# main.net
KiCad netlist of a schematic drawn in Altium Designer
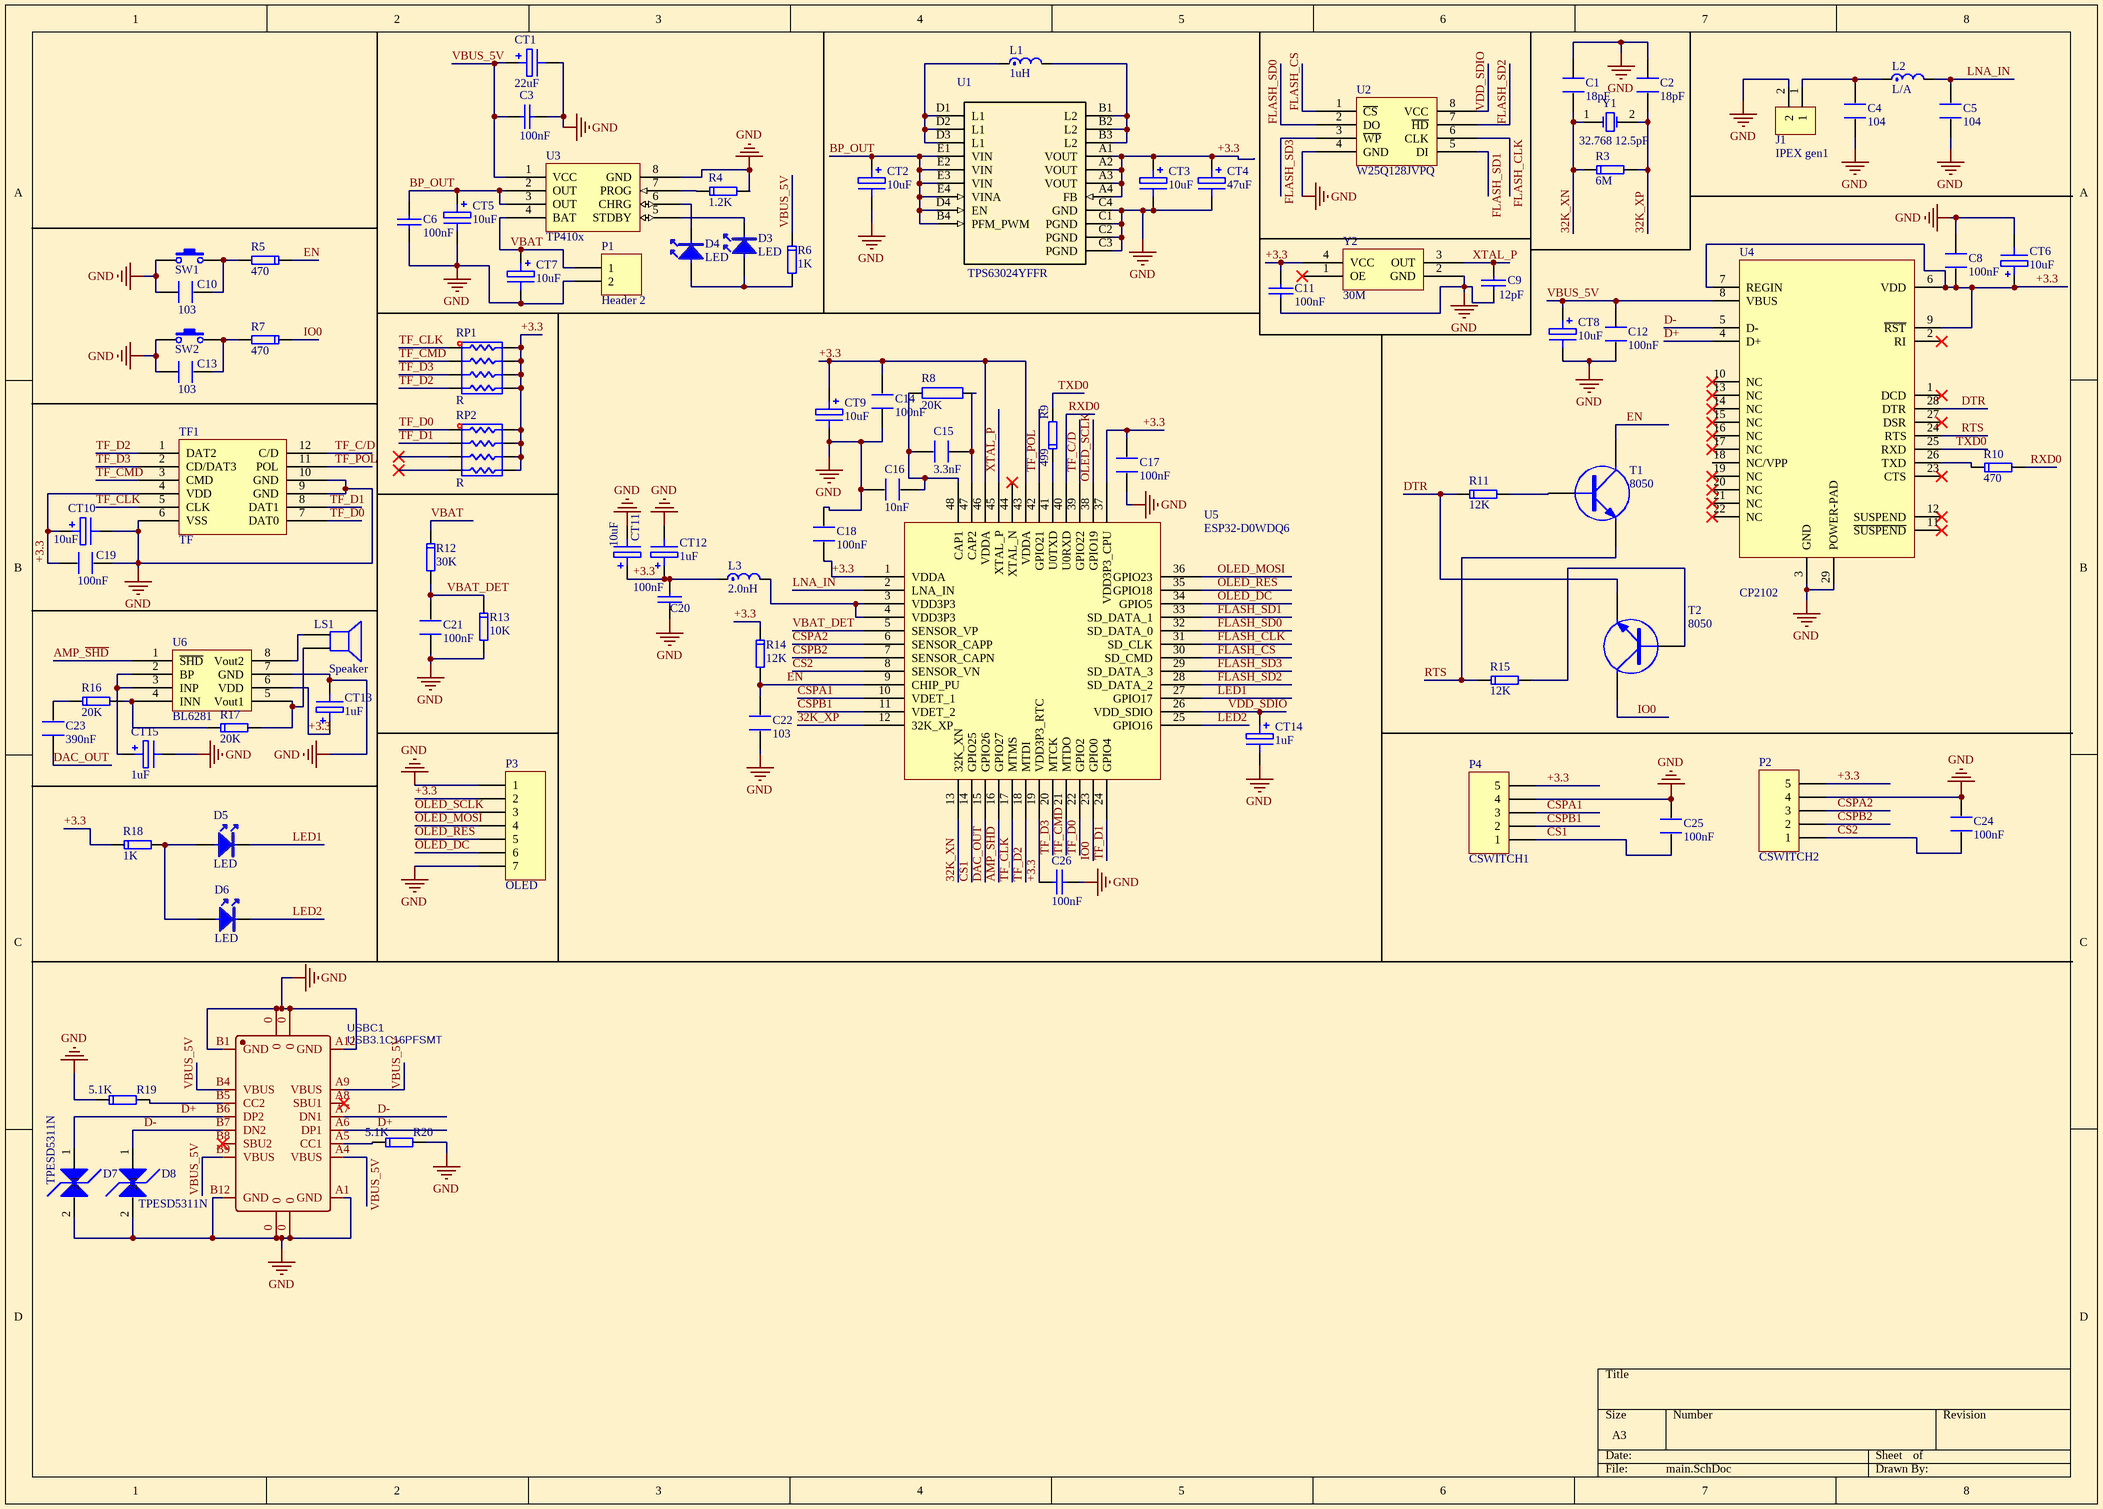
[diagram p0: main.SchDoc]

(export (version "E")
  (design (tool "Eeschema 10.0.6"))
  (components
    (comp (ref "C1") (value "18pF") (footprint "C0603") (libsource (lib "常用2") (part "Capacitor")))
    (comp (ref "C2") (value "18pF") (footprint "C0603") (libsource (lib "常用2") (part "Capacitor")))
    (comp (ref "C3") (value "100nF") (footprint "C0603") (libsource (lib "常用") (part "CAP1")))
    (comp (ref "C4") (value "104") (footprint "C0603") (libsource (lib "常用2") (part "Capacitor")))
    (comp (ref "C5") (value "104") (footprint "C0603") (libsource (lib "常用2") (part "Capacitor")))
    (comp (ref "C6") (value "100nF") (footprint "C0603") (libsource (lib "常用") (part "CAP1")))
    (comp (ref "C8") (value "100nF") (footprint "C0603") (libsource (lib "常用") (part "Capacitor")))
    (comp (ref "C9") (value "12pF") (footprint "C0603") (libsource (lib "常用") (part "CAP1")))
    (comp (ref "C10") (value "103") (footprint "C0603") (libsource (lib "常用2") (part "Capacitor")))
    (comp (ref "C11") (value "100nF") (footprint "C0603") (libsource (lib "常用") (part "CAP1")))
    (comp (ref "C12") (value "100nF") (footprint "C0603") (libsource (lib "常用") (part "Capacitor")))
    (comp (ref "C13") (value "103") (footprint "C0603") (libsource (lib "常用2") (part "Capacitor")))
    (comp (ref "C14") (value "100nF") (footprint "C0603") (libsource (lib "常用2") (part "Capacitor")))
    (comp (ref "C15") (value "3.3nF") (footprint "C0603") (libsource (lib "常用") (part "Capacitor")))
    (comp (ref "C16") (value "10nF") (footprint "C0603") (libsource (lib "常用") (part "Capacitor")))
    (comp (ref "C17") (value "100nF") (footprint "C0603") (libsource (lib "常用2") (part "Capacitor")))
    (comp (ref "C18") (value "100nF") (footprint "C0603") (libsource (lib "常用2") (part "Capacitor")))
    (comp (ref "C19") (value "100nF") (footprint "C0603") (libsource (lib "常用") (part "Capacitor")))
    (comp (ref "C20") (value "100nF") (footprint "C0603") (libsource (lib "常用") (part "CAP1")))
    (comp (ref "C21") (value "100nF") (footprint "C0603") (libsource (lib "常用") (part "Capacitor")))
    (comp (ref "C22") (value "103") (footprint "C0603") (libsource (lib "常用2") (part "Capacitor")))
    (comp (ref "C23") (value "390nF") (footprint "C0603") (libsource (lib "常用2") (part "Capacitor")))
    (comp (ref "C24") (value "100nF") (footprint "C0603") (libsource (lib "常用") (part "Capacitor")))
    (comp (ref "C25") (value "100nF") (footprint "C0603") (libsource (lib "常用") (part "Capacitor")))
    (comp (ref "C26") (value "100nF") (footprint "C0603") (libsource (lib "常用") (part "CAP1")))
    (comp (ref "CT1") (value "22uF") (footprint "C1206") (libsource (lib "常用") (part "CAP Tantalum")))
    (comp (ref "CT2") (value "10uF") (footprint "C1206") (libsource (lib "常用") (part "CAP Tantalum")))
    (comp (ref "CT3") (value "10uF") (footprint "C1206") (libsource (lib "常用") (part "CAP Tantalum")))
    (comp (ref "CT4") (value "47uF") (footprint "C1206") (libsource (lib "常用") (part "CAP Tantalum")))
    (comp (ref "CT5") (value "10uF") (footprint "C1206") (libsource (lib "常用") (part "CAP Tantalum")))
    (comp (ref "CT6") (value "10uF") (footprint "C1206") (libsource (lib "常用") (part "CAP Tantalum")))
    (comp (ref "CT7") (value "10uF") (footprint "C1206") (libsource (lib "常用") (part "CAP Tantalum")))
    (comp (ref "CT8") (value "10uF") (footprint "C1206") (libsource (lib "常用") (part "CAP Tantalum")))
    (comp (ref "CT9") (value "10uF") (footprint "C1206") (libsource (lib "常用") (part "CAP Tantalum")))
    (comp (ref "CT10") (value "10uF") (footprint "C1206") (libsource (lib "常用") (part "CAP Tantalum")))
    (comp (ref "CT11") (value "10uF") (footprint "C1206") (libsource (lib "常用") (part "CAP Tantalum")))
    (comp (ref "CT12") (value "1uF") (footprint "C1206") (libsource (lib "常用") (part "CAP Tantalum")))
    (comp (ref "CT13") (value "1uF") (footprint "C1206") (libsource (lib "常用") (part "CAP Tantalum")))
    (comp (ref "CT14") (value "1uF") (footprint "C1206") (libsource (lib "常用") (part "CAP Tantalum")))
    (comp (ref "CT15") (value "1uF") (footprint "C1206") (libsource (lib "常用") (part "CAP Tantalum")))
    (comp (ref "D3") (value "LED") (footprint "LED_1206") (libsource (lib "常用") (part "LED")))
    (comp (ref "D4") (value "LED") (footprint "LED_1206") (libsource (lib "常用") (part "LED")))
    (comp (ref "D5") (value "LED") (footprint "LED_1206") (libsource (lib "常用") (part "LED")))
    (comp (ref "D6") (value "LED") (footprint "LED_1206") (libsource (lib "常用") (part "LED")))
    (comp (ref "D7") (value "TPESD5311N") (footprint "DFN1006-2") (libsource (lib "常用2") (part "TPESD5311N")))
    (comp (ref "D8") (value "TPESD5311N") (footprint "DFN1006-2") (libsource (lib "常用2") (part "TPESD5311N")))
    (comp (ref "J1") (value "IPEX gen1") (footprint "IPEX gen1") (libsource (lib "常用2") (part "IPEX gen1")))
    (comp (ref "L1") (value "1uH") (footprint "L0520") (libsource (lib "常用") (part "INDUTOR")))
    (comp (ref "L2") (value "L/A") (footprint "L0603") (libsource (lib "常用") (part "INDUTOR")))
    (comp (ref "L3") (value "2.0nH") (footprint "L0603") (libsource (lib "常用") (part "INDUTOR")))
    (comp (ref "LS1")
      (value "Speaker")
      (footprint "PIN2")
      (description "Loudspeaker")
      (fields (field (name "PUBLISHER") "Altium Limited"))
      (libsource (lib "Miscellaneous Devices") (part "Speaker"))
    )
    (comp (ref "P1")
      (value "Header 2")
      (footprint "HDR1X2")
      (description "Header, 2-Pin")
      (fields (field (name "PUBLISHER") "Altium Limited"))
      (libsource (lib "Miscellaneous Connectors") (part "Header 2"))
    )
    (comp (ref "P2")
      (value "CSWITCH2")
      (footprint "HDR1X5")
      (description "Header, 5-Pin")
      (fields (field (name "PUBLISHER") "Altium Limited"))
      (libsource (lib "Miscellaneous Connectors") (part "Header 5"))
    )
    (comp (ref "P3")
      (value "OLED")
      (footprint "HDR1X7")
      (description "Header, 7-Pin")
      (fields (field (name "PUBLISHER") "Altium Limited"))
      (libsource (lib "Miscellaneous Connectors") (part "Header 7"))
    )
    (comp (ref "P4")
      (value "CSWITCH1")
      (footprint "HDR1X5")
      (description "Header, 5-Pin")
      (fields (field (name "PUBLISHER") "Altium Limited"))
      (libsource (lib "Miscellaneous Connectors") (part "Header 5"))
    )
    (comp (ref "R3") (value "6M") (footprint "R0603") (libsource (lib "常用2") (part "Resistor")))
    (comp (ref "R4") (value "1.2K") (footprint "R0603") (libsource (lib "常用") (part "Resistor")))
    (comp (ref "R5") (value "470") (footprint "R0603") (libsource (lib "常用2") (part "Resistor")))
    (comp (ref "R6") (value "1K") (footprint "R0603") (libsource (lib "常用") (part "Resistor")))
    (comp (ref "R7") (value "470") (footprint "R0603") (libsource (lib "常用2") (part "Resistor")))
    (comp (ref "R8") (value "20K") (footprint "0603") (description "电阻") (libsource (lib "常用") (part "RES")))
    (comp (ref "R9") (value "499") (footprint "R0603") (libsource (lib "常用") (part "Resistor")))
    (comp (ref "R10") (value "470") (footprint "R0603") (libsource (lib "常用") (part "Resistor")))
    (comp (ref "R11") (value "12K") (footprint "R0603") (libsource (lib "常用") (part "Resistor")))
    (comp (ref "R12") (value "30K") (footprint "R0603") (libsource (lib "常用2") (part "Resistor")))
    (comp (ref "R13") (value "10K") (footprint "R0603") (libsource (lib "常用2") (part "Resistor")))
    (comp (ref "R14") (value "12K") (footprint "R0603") (libsource (lib "常用2") (part "Resistor")))
    (comp (ref "R15") (value "12K") (footprint "R0603") (libsource (lib "常用") (part "Resistor")))
    (comp (ref "R16") (value "20K") (footprint "R0603") (libsource (lib "常用2") (part "Resistor")))
    (comp (ref "R17") (value "20K") (footprint "R0603") (libsource (lib "常用2") (part "Resistor")))
    (comp (ref "R18") (value "1K") (footprint "R0603") (libsource (lib "常用2") (part "Resistor")))
    (comp (ref "R19") (value "5.1K") (footprint "R0603") (libsource (lib "常用") (part "Resistor")))
    (comp (ref "R20") (value "5.1K") (footprint "R0603") (libsource (lib "常用") (part "Resistor")))
    (comp (ref "RP1")
      (value "R")
      (footprint "RP4")
      (description "Isolated Resistor Network")
      (fields (field (name "PUBLISHER") "Altium Limited"))
      (libsource (lib "常用") (part "RP4"))
    )
    (comp (ref "RP2")
      (value "R")
      (footprint "RP4")
      (description "Isolated Resistor Network")
      (fields (field (name "PUBLISHER") "Altium Limited"))
      (libsource (lib "常用") (part "RP4"))
    )
    (comp (ref "SW1")
      (value "switch")
      (footprint "microswitch")
      (description "微动开关")
      (libsource (lib "常用2") (part "microswitch"))
    )
    (comp (ref "SW2")
      (value "switch")
      (footprint "microswitch")
      (description "微动开关")
      (libsource (lib "常用2") (part "microswitch"))
    )
    (comp (ref "T1")
      (value "8050")
      (footprint "STO-23")
      (description "NPN型三极管")
      (libsource (lib "常用") (part "8050"))
    )
    (comp (ref "T2")
      (value "8050")
      (footprint "STO-23")
      (description "NPN型三极管")
      (libsource (lib "常用") (part "8050"))
    )
    (comp (ref "TF1") (value "TF") (footprint "TF_3") (libsource (lib "TF") (part "TF3")))
    (comp (ref "U1")
      (value "TPS63024YFFR")
      (footprint "YFF0020AJAF")
      (description "No Description Available")
      (fields
        (field (name "ALTERNATE_PARTNUMBER") "TPS63024YFFT")
        (field (name "MANUFACTURER") "Texas Instruments")
        (field (name "COPYRIGHT") "Copyright (C) 2018 Accelerated Designs. All rights reserved")
      )
      (libsource (lib "TPS63024YFFR") (part "TPS63024YFFR"))
    )
    (comp (ref "U2")
      (value "W25Q128JVPQ")
      (footprint "WSON-8_5x6mm")
      (libsource (lib "FLASH") (part "W25Q128JVPQ"))
    )
    (comp (ref "U3") (value "TP410x") (footprint "DFN-8_EP_3x3mm") (libsource (lib "TP4102") (part "TP410x")))
    (comp (ref "U4")
      (value "CP2102")
      (footprint "QFN-28")
      (description "USB to TTL")
      (libsource (lib "常用2") (part "CP2102"))
    )
    (comp (ref "U5")
      (value "ESP32-D0WDQ6")
      (footprint "QFN-48_6x6x04P")
      (libsource (lib "ESP32") (part "ESP32-D0WDQ6"))
    )
    (comp (ref "U6")
      (value "BL6281")
      (footprint "MSOP-8")
      (description "国产功放")
      (libsource (lib "常用2") (part "BL6281"))
    )
    (comp (ref "USBC1")
      (value "USB3.1C16PFSMT")
      (footprint "TYPE-C-USB-17")
      (libsource (lib "type-c-m") (part "USB3.1C16PFSMT"))
    )
    (comp (ref "Y1")
      (value "32.768 12.5pF")
      (footprint "SMD-3215_2P FC - 135")
      (description "Crystal Oscillator")
      (libsource (lib "常用晶振") (part "XTAL"))
    )
    (comp (ref "Y2")
      (value "30M")
      (footprint "SMD-2016-4P")
      (description "Simple Package Xtal Oscillator")
      (libsource (lib "常用晶振") (part "XTAL-SPXO"))
    )
  )
  (nets
    (net (code "1") (name "/+3.3") (class "Default")
      (node (ref "C11") (pin "2") (pinfunction "2_2") (pintype "passive"))
      (node (ref "C14") (pin "2") (pintype "passive"))
      (node (ref "C17") (pin "2") (pintype "passive"))
      (node (ref "C18") (pin "1") (pintype "passive"))
      (node (ref "C19") (pin "2") (pintype "passive"))
      (node (ref "C20") (pin "1") (pinfunction "1_1") (pintype "passive"))
      (node (ref "C26") (pin "1") (pinfunction "1_1") (pintype "passive"))
      (node (ref "C8") (pin "1") (pintype "passive"))
      (node (ref "CT10") (pin "1") (pinfunction "1_1") (pintype "passive"))
      (node (ref "CT11") (pin "1") (pinfunction "1_1") (pintype "passive"))
      (node (ref "CT12") (pin "1") (pinfunction "1_1") (pintype "passive"))
      (node (ref "CT13") (pin "1") (pinfunction "1_1") (pintype "passive"))
      (node (ref "CT3") (pin "1") (pinfunction "1_1") (pintype "passive"))
      (node (ref "CT4") (pin "1") (pinfunction "1_1") (pintype "passive"))
      (node (ref "CT6") (pin "1") (pinfunction "1_1") (pintype "passive"))
      (node (ref "CT9") (pin "1") (pinfunction "1_1") (pintype "passive"))
      (node (ref "L3") (pin "1") (pinfunction "1_1") (pintype "passive"))
      (node (ref "P2") (pin "5") (pinfunction "5_5") (pintype "passive"))
      (node (ref "P3") (pin "2") (pinfunction "2_2") (pintype "passive"))
      (node (ref "P4") (pin "5") (pinfunction "5_5") (pintype "passive"))
      (node (ref "R14") (pin "1") (pinfunction "1_1") (pintype "passive"))
      (node (ref "R18") (pin "1") (pinfunction "1_1") (pintype "passive"))
      (node (ref "RP1") (pin "5") (pinfunction "5_5") (pintype "passive"))
      (node (ref "RP1") (pin "6") (pinfunction "6_6") (pintype "passive"))
      (node (ref "RP1") (pin "7") (pinfunction "7_7") (pintype "passive"))
      (node (ref "RP1") (pin "8") (pinfunction "8_8") (pintype "passive"))
      (node (ref "RP2") (pin "5") (pinfunction "5_5") (pintype "passive"))
      (node (ref "RP2") (pin "6") (pinfunction "6_6") (pintype "passive"))
      (node (ref "RP2") (pin "7") (pinfunction "7_7") (pintype "passive"))
      (node (ref "RP2") (pin "8") (pinfunction "8_8") (pintype "passive"))
      (node (ref "TF1") (pin "4") (pinfunction "VDD_4") (pintype "passive"))
      (node (ref "U1") (pin "A1") (pinfunction "VOUT_A1") (pintype "power_in"))
      (node (ref "U1") (pin "A2") (pinfunction "VOUT_A2") (pintype "power_in"))
      (node (ref "U1") (pin "A3") (pinfunction "VOUT_A3") (pintype "power_in"))
      (node (ref "U1") (pin "A4") (pinfunction "FB_A4") (pintype "input"))
      (node (ref "U4") (pin "6") (pinfunction "VDD_6") (pintype "passive"))
      (node (ref "U4") (pin "7") (pinfunction "REGIN_7") (pintype "passive"))
      (node (ref "U4") (pin "9") (pinfunction "~{RST}_9") (pintype "passive"))
      (node (ref "U5") (pin "1") (pinfunction "VDDA_1") (pintype "passive"))
      (node (ref "U5") (pin "19") (pinfunction "VDD3P3_RTC_19") (pintype "passive"))
      (node (ref "U5") (pin "37") (pinfunction "VDD3P3_CPU_37") (pintype "passive"))
      (node (ref "U5") (pin "43") (pinfunction "VDDA_43") (pintype "passive"))
      (node (ref "U5") (pin "46") (pinfunction "VDDA_46") (pintype "passive"))
      (node (ref "U6") (pin "6") (pinfunction "VDD_6") (pintype "passive"))
      (node (ref "Y2") (pin "4") (pinfunction "VCC_4") (pintype "passive"))
    )
    (net (code "2") (name "/32K_XN") (class "Default")
      (node (ref "C1") (pin "2") (pintype "passive"))
      (node (ref "R3") (pin "1") (pinfunction "1_1") (pintype "passive"))
      (node (ref "U5") (pin "13") (pinfunction "32K_XN_13") (pintype "passive"))
      (node (ref "Y1") (pin "1") (pinfunction "1_1") (pintype "passive"))
    )
    (net (code "3") (name "/32K_XP") (class "Default")
      (node (ref "C2") (pin "2") (pintype "passive"))
      (node (ref "R3") (pin "2") (pinfunction "2_2") (pintype "passive"))
      (node (ref "U5") (pin "12") (pinfunction "32K_XP_12") (pintype "passive"))
      (node (ref "Y1") (pin "2") (pinfunction "2_2") (pintype "passive"))
    )
    (net (code "4") (name "/AMP_~{SHD}") (class "Default")
      (node (ref "U5") (pin "16") (pinfunction "GPIO27_16") (pintype "passive"))
      (node (ref "U6") (pin "1") (pinfunction "~{SHD}_1") (pintype "passive"))
    )
    (net (code "5") (name "/BP_OUT") (class "Default")
      (node (ref "C6") (pin "2") (pinfunction "2_2") (pintype "passive"))
      (node (ref "CT2") (pin "1") (pinfunction "1_1") (pintype "passive"))
      (node (ref "CT5") (pin "1") (pinfunction "1_1") (pintype "passive"))
      (node (ref "U1") (pin "B4") (pinfunction "PFM_PWM_B4") (pintype "input"))
      (node (ref "U1") (pin "D4") (pinfunction "EN_D4") (pintype "input"))
      (node (ref "U1") (pin "E1") (pinfunction "VIN_E1") (pintype "power_in"))
      (node (ref "U1") (pin "E2") (pinfunction "VIN_E2") (pintype "power_in"))
      (node (ref "U1") (pin "E3") (pinfunction "VIN_E3") (pintype "power_in"))
      (node (ref "U1") (pin "E4") (pinfunction "VINA_E4") (pintype "input"))
      (node (ref "U3") (pin "2") (pinfunction "OUT_2") (pintype "power_in"))
      (node (ref "U3") (pin "3") (pinfunction "OUT_3") (pintype "power_in"))
    )
    (net (code "6") (name "/CS1") (class "Default")
      (node (ref "C25") (pin "2") (pintype "passive"))
      (node (ref "P4") (pin "1") (pinfunction "1_1") (pintype "passive"))
      (node (ref "U5") (pin "14") (pinfunction "GPIO25_14") (pintype "passive"))
    )
    (net (code "7") (name "/CS2") (class "Default")
      (node (ref "C24") (pin "2") (pintype "passive"))
      (node (ref "P2") (pin "1") (pinfunction "1_1") (pintype "passive"))
      (node (ref "U5") (pin "8") (pinfunction "SENSOR_VN_8") (pintype "passive"))
    )
    (net (code "8") (name "/CSPA1") (class "Default")
      (node (ref "P4") (pin "3") (pinfunction "3_3") (pintype "passive"))
      (node (ref "U5") (pin "10") (pinfunction "VDET_1_10") (pintype "passive"))
    )
    (net (code "9") (name "/CSPA2") (class "Default")
      (node (ref "P2") (pin "3") (pinfunction "3_3") (pintype "passive"))
      (node (ref "U5") (pin "6") (pinfunction "SENSOR_CAPP_6") (pintype "passive"))
    )
    (net (code "10") (name "/CSPB1") (class "Default")
      (node (ref "P4") (pin "2") (pinfunction "2_2") (pintype "passive"))
      (node (ref "U5") (pin "11") (pinfunction "VDET_2_11") (pintype "passive"))
    )
    (net (code "11") (name "/CSPB2") (class "Default")
      (node (ref "P2") (pin "2") (pinfunction "2_2") (pintype "passive"))
      (node (ref "U5") (pin "7") (pinfunction "SENSOR_CAPN_7") (pintype "passive"))
    )
    (net (code "12") (name "/D+") (class "Default")
      (node (ref "D7") (pin "1") (pinfunction "1_1") (pintype "passive"))
      (node (ref "U4") (pin "4") (pinfunction "D+_4") (pintype "passive"))
      (node (ref "USBC1") (pin "A6") (pinfunction "DP1_A6") (pintype "passive"))
      (node (ref "USBC1") (pin "B6") (pinfunction "DP2_B6") (pintype "passive"))
    )
    (net (code "13") (name "/D-") (class "Default")
      (node (ref "D8") (pin "1") (pinfunction "1_1") (pintype "passive"))
      (node (ref "U4") (pin "5") (pinfunction "D-_5") (pintype "passive"))
      (node (ref "USBC1") (pin "A7") (pinfunction "DN1_A7") (pintype "passive"))
      (node (ref "USBC1") (pin "B7") (pinfunction "DN2_B7") (pintype "passive"))
    )
    (net (code "14") (name "/DAC_OUT") (class "Default")
      (node (ref "C23") (pin "1") (pintype "passive"))
      (node (ref "U5") (pin "15") (pinfunction "GPIO26_15") (pintype "passive"))
    )
    (net (code "15") (name "/DTR") (class "Default")
      (node (ref "R11") (pin "1") (pinfunction "1_1") (pintype "passive"))
      (node (ref "T2") (pin "1") (pinfunction "E_1") (pintype "passive"))
      (node (ref "U4") (pin "28") (pinfunction "DTR_28") (pintype "passive"))
    )
    (net (code "16") (name "/EN") (class "Default")
      (node (ref "C22") (pin "2") (pintype "passive"))
      (node (ref "R14") (pin "2") (pinfunction "2_2") (pintype "passive"))
      (node (ref "R5") (pin "1") (pinfunction "1_1") (pintype "passive"))
      (node (ref "T1") (pin "3") (pinfunction "C_3") (pintype "passive"))
      (node (ref "U5") (pin "9") (pinfunction "CHIP_PU_9") (pintype "passive"))
    )
    (net (code "17") (name "/FLASH_CLK") (class "Default")
      (node (ref "U2") (pin "6") (pinfunction "CLK_6") (pintype "passive"))
      (node (ref "U5") (pin "31") (pinfunction "SD_CLK_31") (pintype "passive"))
    )
    (net (code "18") (name "/FLASH_CS") (class "Default")
      (node (ref "U2") (pin "1") (pinfunction "~{CS}_1") (pintype "passive"))
      (node (ref "U5") (pin "30") (pinfunction "SD_CMD_30") (pintype "passive"))
    )
    (net (code "19") (name "/FLASH_SD0") (class "Default")
      (node (ref "U2") (pin "2") (pinfunction "DO_2") (pintype "passive"))
      (node (ref "U5") (pin "32") (pinfunction "SD_DATA_0_32") (pintype "passive"))
    )
    (net (code "20") (name "/FLASH_SD1") (class "Default")
      (node (ref "U2") (pin "5") (pinfunction "DI_5") (pintype "passive"))
      (node (ref "U5") (pin "33") (pinfunction "SD_DATA_1_33") (pintype "passive"))
    )
    (net (code "21") (name "/FLASH_SD2") (class "Default")
      (node (ref "U2") (pin "7") (pinfunction "~{HD}_7") (pintype "passive"))
      (node (ref "U5") (pin "28") (pinfunction "SD_DATA_2_28") (pintype "passive"))
    )
    (net (code "22") (name "/FLASH_SD3") (class "Default")
      (node (ref "U2") (pin "3") (pinfunction "~{WP}_3") (pintype "passive"))
      (node (ref "U5") (pin "29") (pinfunction "SD_DATA_3_29") (pintype "passive"))
    )
    (net (code "23") (name "/IO0") (class "Default")
      (node (ref "R7") (pin "1") (pinfunction "1_1") (pintype "passive"))
      (node (ref "T2") (pin "3") (pinfunction "C_3") (pintype "passive"))
      (node (ref "U5") (pin "23") (pinfunction "GPIO0_23") (pintype "passive"))
    )
    (net (code "24") (name "/LED1") (class "Default")
      (node (ref "D5") (pin "2") (pinfunction "2_2") (pintype "passive"))
      (node (ref "U5") (pin "27") (pinfunction "GPIO17_27") (pintype "passive"))
    )
    (net (code "25") (name "/LED2") (class "Default")
      (node (ref "D6") (pin "2") (pinfunction "2_2") (pintype "passive"))
      (node (ref "U5") (pin "25") (pinfunction "GPIO16_25") (pintype "passive"))
    )
    (net (code "26") (name "/LNA_IN") (class "Default")
      (node (ref "C5") (pin "2") (pintype "passive"))
      (node (ref "L2") (pin "2") (pinfunction "2_2") (pintype "passive"))
      (node (ref "U5") (pin "2") (pinfunction "LNA_IN_2") (pintype "passive"))
    )
    (net (code "27") (name "/OLED_DC") (class "Default")
      (node (ref "P3") (pin "6") (pinfunction "6_6") (pintype "passive"))
      (node (ref "U5") (pin "34") (pinfunction "GPIO5_34") (pintype "passive"))
    )
    (net (code "28") (name "/OLED_MOSI") (class "Default")
      (node (ref "P3") (pin "4") (pinfunction "4_4") (pintype "passive"))
      (node (ref "U5") (pin "36") (pinfunction "GPIO23_36") (pintype "passive"))
    )
    (net (code "29") (name "/OLED_RES") (class "Default")
      (node (ref "P3") (pin "5") (pinfunction "5_5") (pintype "passive"))
      (node (ref "U5") (pin "35") (pinfunction "GPIO18_35") (pintype "passive"))
    )
    (net (code "30") (name "/OLED_SCLK") (class "Default")
      (node (ref "P3") (pin "3") (pinfunction "3_3") (pintype "passive"))
      (node (ref "U5") (pin "38") (pinfunction "GPIO19_38") (pintype "passive"))
    )
    (net (code "31") (name "/RTS") (class "Default")
      (node (ref "R15") (pin "1") (pinfunction "1_1") (pintype "passive"))
      (node (ref "T1") (pin "1") (pinfunction "E_1") (pintype "passive"))
      (node (ref "U4") (pin "24") (pinfunction "RTS_24") (pintype "passive"))
    )
    (net (code "32") (name "/RXD0") (class "Default")
      (node (ref "R10") (pin "2") (pinfunction "2_2") (pintype "passive"))
      (node (ref "U5") (pin "40") (pinfunction "U0RXD_40") (pintype "passive"))
    )
    (net (code "33") (name "/TF_CLK") (class "Default")
      (node (ref "RP1") (pin "1") (pinfunction "1_1") (pintype "passive"))
      (node (ref "TF1") (pin "5") (pinfunction "CLK_5") (pintype "passive"))
      (node (ref "U5") (pin "17") (pinfunction "MTMS_17") (pintype "passive"))
    )
    (net (code "34") (name "/TF_CMD") (class "Default")
      (node (ref "RP1") (pin "2") (pinfunction "2_2") (pintype "passive"))
      (node (ref "TF1") (pin "3") (pinfunction "CMD_3") (pintype "passive"))
      (node (ref "U5") (pin "21") (pinfunction "MTDO_21") (pintype "passive"))
    )
    (net (code "35") (name "/TF_C{slash}D") (class "Default")
      (node (ref "TF1") (pin "12") (pinfunction "C/D_12") (pintype "passive"))
      (node (ref "U5") (pin "39") (pinfunction "GPIO22_39") (pintype "passive"))
    )
    (net (code "36") (name "/TF_D0") (class "Default")
      (node (ref "RP2") (pin "1") (pinfunction "1_1") (pintype "passive"))
      (node (ref "TF1") (pin "7") (pinfunction "DAT0_7") (pintype "passive"))
      (node (ref "U5") (pin "22") (pinfunction "GPIO2_22") (pintype "passive"))
    )
    (net (code "37") (name "/TF_D1") (class "Default")
      (node (ref "RP2") (pin "2") (pinfunction "2_2") (pintype "passive"))
      (node (ref "TF1") (pin "8") (pinfunction "DAT1_8") (pintype "passive"))
      (node (ref "U5") (pin "24") (pinfunction "GPIO4_24") (pintype "passive"))
    )
    (net (code "38") (name "/TF_D2") (class "Default")
      (node (ref "RP1") (pin "4") (pinfunction "4_4") (pintype "passive"))
      (node (ref "TF1") (pin "1") (pinfunction "DAT2_1") (pintype "passive"))
      (node (ref "U5") (pin "18") (pinfunction "MTDI_18") (pintype "passive"))
    )
    (net (code "39") (name "/TF_D3") (class "Default")
      (node (ref "RP1") (pin "3") (pinfunction "3_3") (pintype "passive"))
      (node (ref "TF1") (pin "2") (pinfunction "CD/DAT3_2") (pintype "passive"))
      (node (ref "U5") (pin "20") (pinfunction "MTCK_20") (pintype "passive"))
    )
    (net (code "40") (name "/TF_POL") (class "Default")
      (node (ref "TF1") (pin "11") (pinfunction "POL_11") (pintype "passive"))
      (node (ref "U5") (pin "42") (pinfunction "GPIO21_42") (pintype "passive"))
    )
    (net (code "41") (name "/TXD0") (class "Default")
      (node (ref "R9") (pin "2") (pinfunction "2_2") (pintype "passive"))
      (node (ref "U4") (pin "25") (pinfunction "RXD_25") (pintype "passive"))
    )
    (net (code "42") (name "/VBAT") (class "Default")
      (node (ref "CT7") (pin "1") (pinfunction "1_1") (pintype "passive"))
      (node (ref "P1") (pin "1") (pinfunction "1_1") (pintype "passive"))
      (node (ref "R12") (pin "1") (pinfunction "1_1") (pintype "passive"))
      (node (ref "U3") (pin "4") (pinfunction "BAT_4") (pintype "power_in"))
    )
    (net (code "43") (name "/VBAT_DET") (class "Default")
      (node (ref "C21") (pin "1") (pintype "passive"))
      (node (ref "R12") (pin "2") (pinfunction "2_2") (pintype "passive"))
      (node (ref "R13") (pin "1") (pinfunction "1_1") (pintype "passive"))
      (node (ref "U5") (pin "5") (pinfunction "SENSOR_VP_5") (pintype "passive"))
    )
    (net (code "44") (name "/VBUS_5V") (class "Default")
      (node (ref "C12") (pin "2") (pintype "passive"))
      (node (ref "C3") (pin "1") (pinfunction "1_1") (pintype "passive"))
      (node (ref "CT1") (pin "1") (pinfunction "1_1") (pintype "passive"))
      (node (ref "CT8") (pin "1") (pinfunction "1_1") (pintype "passive"))
      (node (ref "R6") (pin "1") (pinfunction "1_1") (pintype "passive"))
      (node (ref "U3") (pin "1") (pinfunction "VCC_1") (pintype "passive"))
      (node (ref "U4") (pin "8") (pinfunction "VBUS_8") (pintype "passive"))
      (node (ref "USBC1") (pin "A4") (pinfunction "VBUS_A4") (pintype "passive"))
      (node (ref "USBC1") (pin "A9") (pinfunction "VBUS_A9") (pintype "passive"))
      (node (ref "USBC1") (pin "B4") (pinfunction "VBUS_B4") (pintype "passive"))
      (node (ref "USBC1") (pin "B9") (pinfunction "VBUS_B9") (pintype "passive"))
    )
    (net (code "45") (name "/VDD_SDIO") (class "Default")
      (node (ref "CT14") (pin "1") (pinfunction "1_1") (pintype "passive"))
      (node (ref "U2") (pin "8") (pinfunction "VCC_8") (pintype "passive"))
      (node (ref "U5") (pin "26") (pinfunction "VDD_SDIO_26") (pintype "passive"))
    )
    (net (code "46") (name "/XTAL_P") (class "Default")
      (node (ref "C9") (pin "2") (pinfunction "2_2") (pintype "passive"))
      (node (ref "U5") (pin "45") (pinfunction "XTAL_P_45") (pintype "passive"))
      (node (ref "Y2") (pin "3") (pinfunction "OUT_3") (pintype "passive"))
    )
    (net (code "47") (name "GND") (class "Default")
      (node (ref "C1") (pin "1") (pintype "passive"))
      (node (ref "C10") (pin "1") (pintype "passive"))
      (node (ref "C11") (pin "1") (pinfunction "1_1") (pintype "passive"))
      (node (ref "C12") (pin "1") (pintype "passive"))
      (node (ref "C13") (pin "1") (pintype "passive"))
      (node (ref "C14") (pin "1") (pintype "passive"))
      (node (ref "C16") (pin "2") (pintype "passive"))
      (node (ref "C17") (pin "1") (pintype "passive"))
      (node (ref "C18") (pin "2") (pintype "passive"))
      (node (ref "C19") (pin "1") (pintype "passive"))
      (node (ref "C2") (pin "1") (pintype "passive"))
      (node (ref "C20") (pin "2") (pinfunction "2_2") (pintype "passive"))
      (node (ref "C21") (pin "2") (pintype "passive"))
      (node (ref "C22") (pin "1") (pintype "passive"))
      (node (ref "C24") (pin "1") (pintype "passive"))
      (node (ref "C25") (pin "1") (pintype "passive"))
      (node (ref "C26") (pin "2") (pinfunction "2_2") (pintype "passive"))
      (node (ref "C3") (pin "2") (pinfunction "2_2") (pintype "passive"))
      (node (ref "C4") (pin "1") (pintype "passive"))
      (node (ref "C5") (pin "1") (pintype "passive"))
      (node (ref "C6") (pin "1") (pinfunction "1_1") (pintype "passive"))
      (node (ref "C8") (pin "2") (pintype "passive"))
      (node (ref "C9") (pin "1") (pinfunction "1_1") (pintype "passive"))
      (node (ref "CT1") (pin "2") (pinfunction "2_2") (pintype "passive"))
      (node (ref "CT10") (pin "2") (pinfunction "2_2") (pintype "passive"))
      (node (ref "CT11") (pin "2") (pinfunction "2_2") (pintype "passive"))
      (node (ref "CT12") (pin "2") (pinfunction "2_2") (pintype "passive"))
      (node (ref "CT13") (pin "2") (pinfunction "2_2") (pintype "passive"))
      (node (ref "CT14") (pin "2") (pinfunction "2_2") (pintype "passive"))
      (node (ref "CT15") (pin "2") (pinfunction "2_2") (pintype "passive"))
      (node (ref "CT2") (pin "2") (pinfunction "2_2") (pintype "passive"))
      (node (ref "CT3") (pin "2") (pinfunction "2_2") (pintype "passive"))
      (node (ref "CT4") (pin "2") (pinfunction "2_2") (pintype "passive"))
      (node (ref "CT5") (pin "2") (pinfunction "2_2") (pintype "passive"))
      (node (ref "CT6") (pin "2") (pinfunction "2_2") (pintype "passive"))
      (node (ref "CT7") (pin "2") (pinfunction "2_2") (pintype "passive"))
      (node (ref "CT8") (pin "2") (pinfunction "2_2") (pintype "passive"))
      (node (ref "CT9") (pin "2") (pinfunction "2_2") (pintype "passive"))
      (node (ref "D7") (pin "2") (pinfunction "2_2") (pintype "passive"))
      (node (ref "D8") (pin "2") (pinfunction "2_2") (pintype "passive"))
      (node (ref "J1") (pin "2") (pinfunction "2_2") (pintype "passive"))
      (node (ref "P1") (pin "2") (pinfunction "2_2") (pintype "passive"))
      (node (ref "P2") (pin "4") (pinfunction "4_4") (pintype "passive"))
      (node (ref "P3") (pin "1") (pinfunction "1_1") (pintype "passive"))
      (node (ref "P3") (pin "7") (pinfunction "7_7") (pintype "passive"))
      (node (ref "P4") (pin "4") (pinfunction "4_4") (pintype "passive"))
      (node (ref "R13") (pin "2") (pinfunction "2_2") (pintype "passive"))
      (node (ref "R19") (pin "1") (pinfunction "1_1") (pintype "passive"))
      (node (ref "R20") (pin "2") (pinfunction "2_2") (pintype "passive"))
      (node (ref "R4") (pin "2") (pinfunction "2_2") (pintype "passive"))
      (node (ref "SW1") (pin "1") (pinfunction "1_1") (pintype "passive"))
      (node (ref "SW2") (pin "1") (pinfunction "1_1") (pintype "passive"))
      (node (ref "TF1") (pin "10") (pinfunction "GND_10") (pintype "passive"))
      (node (ref "TF1") (pin "6") (pinfunction "VSS_6") (pintype "passive"))
      (node (ref "TF1") (pin "9") (pinfunction "GND_9") (pintype "passive"))
      (node (ref "U1") (pin "C1") (pinfunction "PGND_C1") (pintype "power_in"))
      (node (ref "U1") (pin "C2") (pinfunction "PGND_C2") (pintype "power_in"))
      (node (ref "U1") (pin "C3") (pinfunction "PGND_C3") (pintype "power_in"))
      (node (ref "U1") (pin "C4") (pinfunction "GND_C4") (pintype "power_in"))
      (node (ref "U2") (pin "4") (pinfunction "GND_4") (pintype "passive"))
      (node (ref "U3") (pin "8") (pinfunction "GND_8") (pintype "power_in"))
      (node (ref "U4") (pin "29") (pinfunction "POWER-PAD_29") (pintype "passive"))
      (node (ref "U4") (pin "3") (pinfunction "GND_3") (pintype "passive"))
      (node (ref "U6") (pin "7") (pinfunction "GND_7") (pintype "passive"))
      (node (ref "USBC1") (pin "0") (pinfunction "0_0") (pintype "passive"))
      (node (ref "USBC1") (pin "A1") (pinfunction "GND_A1") (pintype "passive"))
      (node (ref "USBC1") (pin "A12") (pinfunction "GND_A12") (pintype "passive"))
      (node (ref "USBC1") (pin "B1") (pinfunction "GND_B1") (pintype "passive"))
      (node (ref "USBC1") (pin "B12") (pinfunction "GND_B12") (pintype "passive"))
      (node (ref "Y2") (pin "2") (pinfunction "GND_2") (pintype "passive"))
    )
    (net (code "48") (name "Net-(C4-Pad2)") (class "Default")
      (node (ref "C4") (pin "2") (pintype "passive"))
      (node (ref "J1") (pin "1") (pinfunction "1_1") (pintype "passive"))
      (node (ref "L2") (pin "1") (pinfunction "1_1") (pintype "passive"))
    )
    (net (code "49") (name "Net-(C10-Pad2)") (class "Default")
      (node (ref "C10") (pin "2") (pintype "passive"))
      (node (ref "R5") (pin "2") (pinfunction "2_2") (pintype "passive"))
      (node (ref "SW1") (pin "2") (pinfunction "2_2") (pintype "passive"))
    )
    (net (code "50") (name "Net-(C13-Pad2)") (class "Default")
      (node (ref "C13") (pin "2") (pintype "passive"))
      (node (ref "R7") (pin "2") (pinfunction "2_2") (pintype "passive"))
      (node (ref "SW2") (pin "2") (pinfunction "2_2") (pintype "passive"))
    )
    (net (code "51") (name "Net-(C23-Pad2)") (class "Default")
      (node (ref "C23") (pin "2") (pintype "passive"))
      (node (ref "R16") (pin "1") (pinfunction "1_1") (pintype "passive"))
    )
    (net (code "52") (name "Net-(D3-Pad1)") (class "Default")
      (node (ref "D3") (pin "1") (pinfunction "1_1") (pintype "passive"))
      (node (ref "D4") (pin "1") (pinfunction "1_1") (pintype "passive"))
      (node (ref "R6") (pin "2") (pinfunction "2_2") (pintype "passive"))
    )
    (net (code "53") (name "Net-(D5-Pad1)") (class "Default")
      (node (ref "D5") (pin "1") (pinfunction "1_1") (pintype "passive"))
      (node (ref "D6") (pin "1") (pinfunction "1_1") (pintype "passive"))
      (node (ref "R18") (pin "2") (pinfunction "2_2") (pintype "passive"))
    )
    (net (code "54") (name "Net-(L1-Pad1)") (class "Default")
      (node (ref "L1") (pin "1") (pinfunction "1_1") (pintype "passive"))
      (node (ref "U1") (pin "D1") (pinfunction "L1_D1") (pintype "passive"))
      (node (ref "U1") (pin "D2") (pinfunction "L1_D2") (pintype "passive"))
      (node (ref "U1") (pin "D3") (pinfunction "L1_D3") (pintype "passive"))
    )
    (net (code "55") (name "Net-(L1-Pad2)") (class "Default")
      (node (ref "L1") (pin "2") (pinfunction "2_2") (pintype "passive"))
      (node (ref "U1") (pin "B1") (pinfunction "L2_B1") (pintype "passive"))
      (node (ref "U1") (pin "B2") (pinfunction "L2_B2") (pintype "passive"))
      (node (ref "U1") (pin "B3") (pinfunction "L2_B3") (pintype "passive"))
    )
    (net (code "56") (name "Net-(L3-Pad2)") (class "Default")
      (node (ref "L3") (pin "2") (pinfunction "2_2") (pintype "passive"))
      (node (ref "U5") (pin "3") (pinfunction "VDD3P3_3") (pintype "passive"))
      (node (ref "U5") (pin "4") (pinfunction "VDD3P3_4") (pintype "passive"))
    )
    (net (code "57") (name "Net-(T1-B)") (class "Default")
      (node (ref "R11") (pin "2") (pinfunction "2_2") (pintype "passive"))
      (node (ref "T1") (pin "2") (pinfunction "B_2") (pintype "passive"))
    )
    (net (code "58") (name "Net-(T2-B)") (class "Default")
      (node (ref "R15") (pin "2") (pinfunction "2_2") (pintype "passive"))
      (node (ref "T2") (pin "2") (pinfunction "B_2") (pintype "passive"))
    )
    (net (code "59") (name "Net-(U3-CHRG)") (class "Default")
      (node (ref "D4") (pin "2") (pinfunction "2_2") (pintype "passive"))
      (node (ref "U3") (pin "6") (pinfunction "CHRG_6") (pintype "bidirectional"))
    )
    (net (code "60") (name "Net-(U3-PROG)") (class "Default")
      (node (ref "R4") (pin "1") (pinfunction "1_1") (pintype "passive"))
      (node (ref "U3") (pin "7") (pinfunction "PROG_7") (pintype "input"))
    )
    (net (code "61") (name "Net-(U3-STDBY)") (class "Default")
      (node (ref "D3") (pin "2") (pinfunction "2_2") (pintype "passive"))
      (node (ref "U3") (pin "5") (pinfunction "STDBY_5") (pintype "bidirectional"))
    )
    (net (code "62") (name "Net-(U4-TXD)") (class "Default")
      (node (ref "R10") (pin "1") (pinfunction "1_1") (pintype "passive"))
      (node (ref "U4") (pin "26") (pinfunction "TXD_26") (pintype "passive"))
    )
    (net (code "63") (name "Net-(U5-CAP1)") (class "Default")
      (node (ref "C15") (pin "1") (pintype "passive"))
      (node (ref "C16") (pin "1") (pintype "passive"))
      (node (ref "R8") (pin "1") (pinfunction "1_1") (pintype "passive"))
      (node (ref "U5") (pin "48") (pinfunction "CAP1_48") (pintype "passive"))
    )
    (net (code "64") (name "Net-(U5-CAP2)") (class "Default")
      (node (ref "C15") (pin "2") (pintype "passive"))
      (node (ref "R8") (pin "2") (pinfunction "2_2") (pintype "passive"))
      (node (ref "U5") (pin "47") (pinfunction "CAP2_47") (pintype "passive"))
    )
    (net (code "65") (name "Net-(U5-U0TXD)") (class "Default")
      (node (ref "R9") (pin "1") (pinfunction "1_1") (pintype "passive"))
      (node (ref "U5") (pin "41") (pinfunction "U0TXD_41") (pintype "passive"))
    )
    (net (code "66") (name "Net-(U6-BP)") (class "Default")
      (node (ref "CT15") (pin "1") (pinfunction "1_1") (pintype "passive"))
      (node (ref "U6") (pin "2") (pinfunction "BP_2") (pintype "passive"))
      (node (ref "U6") (pin "3") (pinfunction "INP_3") (pintype "passive"))
    )
    (net (code "67") (name "Net-(U6-INN)") (class "Default")
      (node (ref "R16") (pin "2") (pinfunction "2_2") (pintype "passive"))
      (node (ref "R17") (pin "1") (pinfunction "1_1") (pintype "passive"))
      (node (ref "U6") (pin "4") (pinfunction "INN_4") (pintype "passive"))
    )
    (net (code "68") (name "Net-(U6-Vout1)") (class "Default")
      (node (ref "LS1") (pin "2") (pinfunction "2_2") (pintype "passive"))
      (node (ref "R17") (pin "2") (pinfunction "2_2") (pintype "passive"))
      (node (ref "U6") (pin "5") (pinfunction "Vout1_5") (pintype "passive"))
    )
    (net (code "69") (name "Net-(U6-Vout2)") (class "Default")
      (node (ref "LS1") (pin "1") (pinfunction "1_1") (pintype "passive"))
      (node (ref "U6") (pin "8") (pinfunction "Vout2_8") (pintype "passive"))
    )
    (net (code "70") (name "Net-(USBC1-CC1)") (class "Default")
      (node (ref "R20") (pin "1") (pinfunction "1_1") (pintype "passive"))
      (node (ref "USBC1") (pin "A5") (pinfunction "CC1_A5") (pintype "passive"))
    )
    (net (code "71") (name "Net-(USBC1-CC2)") (class "Default")
      (node (ref "R19") (pin "2") (pinfunction "2_2") (pintype "passive"))
      (node (ref "USBC1") (pin "B5") (pinfunction "CC2_B5") (pintype "passive"))
    )
    (net (code "72") (name "unconnected-(RP2-Pad3)") (class "Default")
      (node (ref "RP2") (pin "3") (pinfunction "3_3") (pintype "passive+no_connect"))
    )
    (net (code "73") (name "unconnected-(RP2-Pad4)") (class "Default")
      (node (ref "RP2") (pin "4") (pinfunction "4_4") (pintype "passive+no_connect"))
    )
    (net (code "74") (name "unconnected-(U4-CTS-Pad23)") (class "Default")
      (node (ref "U4") (pin "23") (pinfunction "CTS_23") (pintype "passive+no_connect"))
    )
    (net (code "75") (name "unconnected-(U4-DCD-Pad1)") (class "Default")
      (node (ref "U4") (pin "1") (pinfunction "DCD_1") (pintype "passive+no_connect"))
    )
    (net (code "76") (name "unconnected-(U4-DSR-Pad27)") (class "Default")
      (node (ref "U4") (pin "27") (pinfunction "DSR_27") (pintype "passive+no_connect"))
    )
    (net (code "77") (name "unconnected-(U4-NC-Pad10)") (class "Default")
      (node (ref "U4") (pin "10") (pinfunction "NC_10") (pintype "passive+no_connect"))
    )
    (net (code "78") (name "unconnected-(U4-NC-Pad13)") (class "Default")
      (node (ref "U4") (pin "13") (pinfunction "NC_13") (pintype "passive+no_connect"))
    )
    (net (code "79") (name "unconnected-(U4-NC-Pad14)") (class "Default")
      (node (ref "U4") (pin "14") (pinfunction "NC_14") (pintype "passive+no_connect"))
    )
    (net (code "80") (name "unconnected-(U4-NC-Pad15)") (class "Default")
      (node (ref "U4") (pin "15") (pinfunction "NC_15") (pintype "passive+no_connect"))
    )
    (net (code "81") (name "unconnected-(U4-NC-Pad16)") (class "Default")
      (node (ref "U4") (pin "16") (pinfunction "NC_16") (pintype "passive+no_connect"))
    )
    (net (code "82") (name "unconnected-(U4-NC-Pad17)") (class "Default")
      (node (ref "U4") (pin "17") (pinfunction "NC_17") (pintype "passive+no_connect"))
    )
    (net (code "83") (name "unconnected-(U4-NC-Pad19)") (class "Default")
      (node (ref "U4") (pin "19") (pinfunction "NC_19") (pintype "passive+no_connect"))
    )
    (net (code "84") (name "unconnected-(U4-NC-Pad20)") (class "Default")
      (node (ref "U4") (pin "20") (pinfunction "NC_20") (pintype "passive+no_connect"))
    )
    (net (code "85") (name "unconnected-(U4-NC-Pad21)") (class "Default")
      (node (ref "U4") (pin "21") (pinfunction "NC_21") (pintype "passive+no_connect"))
    )
    (net (code "86") (name "unconnected-(U4-NC-Pad22)") (class "Default")
      (node (ref "U4") (pin "22") (pinfunction "NC_22") (pintype "passive+no_connect"))
    )
    (net (code "87") (name "unconnected-(U4-NC{slash}VPP-Pad18)") (class "Default")
      (node (ref "U4") (pin "18") (pinfunction "NC/VPP_18") (pintype "passive"))
    )
    (net (code "88") (name "unconnected-(U4-RI-Pad2)") (class "Default")
      (node (ref "U4") (pin "2") (pinfunction "RI_2") (pintype "passive+no_connect"))
    )
    (net (code "89") (name "unconnected-(U4-SUSPEND-Pad12)") (class "Default")
      (node (ref "U4") (pin "12") (pinfunction "SUSPEND_12") (pintype "passive+no_connect"))
    )
    (net (code "90") (name "unconnected-(U4-~{SUSPEND}-Pad11)") (class "Default")
      (node (ref "U4") (pin "11") (pinfunction "~{SUSPEND}_11") (pintype "passive+no_connect"))
    )
    (net (code "91") (name "unconnected-(U5-XTAL_N-Pad44)") (class "Default")
      (node (ref "U5") (pin "44") (pinfunction "XTAL_N_44") (pintype "passive+no_connect"))
    )
    (net (code "92") (name "unconnected-(USBC1-SBU1-PadA8)") (class "Default")
      (node (ref "USBC1") (pin "A8") (pinfunction "SBU1_A8") (pintype "passive+no_connect"))
    )
    (net (code "93") (name "unconnected-(USBC1-SBU2-PadB8)") (class "Default")
      (node (ref "USBC1") (pin "B8") (pinfunction "SBU2_B8") (pintype "passive+no_connect"))
    )
    (net (code "94") (name "unconnected-(Y2-OE-Pad1)") (class "Default")
      (node (ref "Y2") (pin "1") (pinfunction "OE_1") (pintype "passive+no_connect"))
    )
  )
)
